# CPU.net
KiCad netlist of a schematic drawn in Altium Designer
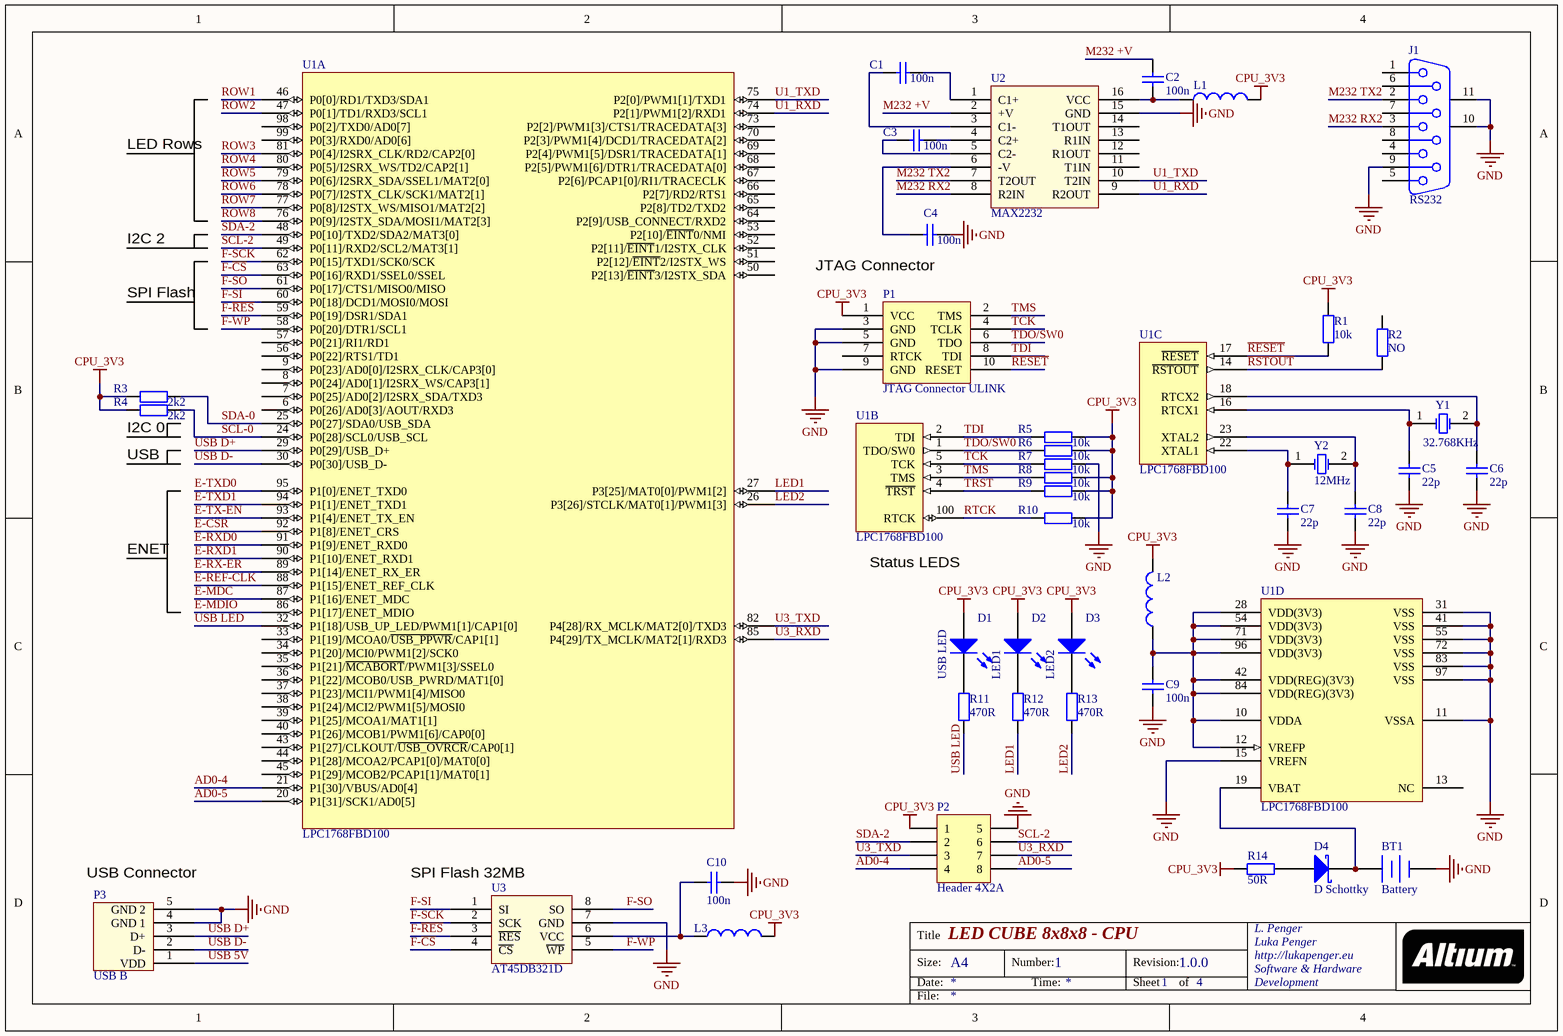
[diagram p0: CPU.SchDoc]

(export (version "E")
  (design (tool "Eeschema 10.0.6"))
  (components
    (comp (ref "BT1")
      (value "Battery")
      (footprint "Battery CAP")
      (description "Multicell Battery")
      (fields (field (name "PUBLISHER") "Altium Limited"))
      (libsource (lib "Miscellaneous Devices") (part "Battery"))
    )
    (comp (ref "C1")
      (value "100n")
      (footprint "1608[0603]")
      (description "Capacitor")
      (fields (field (name "PUBLISHER") "Altium Limited"))
      (libsource (lib "Miscellaneous Devices") (part "Cap"))
    )
    (comp (ref "C2")
      (value "100n")
      (footprint "1608[0603]")
      (description "Capacitor")
      (fields (field (name "PUBLISHER") "Altium Limited"))
      (libsource (lib "Miscellaneous Devices") (part "Cap"))
    )
    (comp (ref "C3")
      (value "100n")
      (footprint "1608[0603]")
      (description "Capacitor")
      (fields (field (name "PUBLISHER") "Altium Limited"))
      (libsource (lib "Miscellaneous Devices") (part "Cap"))
    )
    (comp (ref "C4")
      (value "100n")
      (footprint "1608[0603]")
      (description "Capacitor")
      (fields (field (name "PUBLISHER") "Altium Limited"))
      (libsource (lib "Miscellaneous Devices") (part "Cap"))
    )
    (comp (ref "C5")
      (value "22p")
      (footprint "1608[0603]")
      (description "Capacitor")
      (fields (field (name "PUBLISHER") "Altium Limited"))
      (libsource (lib "Miscellaneous Devices") (part "Cap"))
    )
    (comp (ref "C6")
      (value "22p")
      (footprint "1608[0603]")
      (description "Capacitor")
      (fields (field (name "PUBLISHER") "Altium Limited"))
      (libsource (lib "Miscellaneous Devices") (part "Cap"))
    )
    (comp (ref "C7")
      (value "22p")
      (footprint "1608[0603]")
      (description "Capacitor")
      (fields (field (name "PUBLISHER") "Altium Limited"))
      (libsource (lib "Miscellaneous Devices") (part "Cap"))
    )
    (comp (ref "C8")
      (value "22p")
      (footprint "1608[0603]")
      (description "Capacitor")
      (fields (field (name "PUBLISHER") "Altium Limited"))
      (libsource (lib "Miscellaneous Devices") (part "Cap"))
    )
    (comp (ref "C9")
      (value "100n")
      (footprint "1608[0603]")
      (description "Capacitor")
      (fields (field (name "PUBLISHER") "Altium Limited"))
      (libsource (lib "Miscellaneous Devices") (part "Cap"))
    )
    (comp (ref "C10")
      (value "100n")
      (footprint "1608[0603]")
      (description "Capacitor")
      (fields (field (name "PUBLISHER") "Altium Limited"))
      (libsource (lib "Miscellaneous Devices") (part "Cap"))
    )
    (comp (ref "D1")
      (value "USB LED")
      (footprint "LED-1")
      (description "Typical INFRARED GaAs LED")
      (fields (field (name "PUBLISHER") "Altium Limited"))
      (libsource (lib "Miscellaneous Devices") (part "LED0"))
    )
    (comp (ref "D2")
      (value "LED1")
      (footprint "LED-1")
      (description "Typical INFRARED GaAs LED")
      (fields (field (name "PUBLISHER") "Altium Limited"))
      (libsource (lib "Miscellaneous Devices") (part "LED0"))
    )
    (comp (ref "D3")
      (value "LED2")
      (footprint "LED-1")
      (description "Typical INFRARED GaAs LED")
      (fields (field (name "PUBLISHER") "Altium Limited"))
      (libsource (lib "Miscellaneous Devices") (part "LED0"))
    )
    (comp (ref "D4")
      (value "D Schottky")
      (footprint "SMB")
      (description "Schottky Diode")
      (fields (field (name "PUBLISHER") "Altium Limited"))
      (libsource (lib "Miscellaneous Devices") (part "D Schottky"))
    )
    (comp (ref "J1")
      (value "RS232")
      (footprint "DSUB1.385-2H9")
      (description "Receptacle Assembly, 9 Position, Right Angle")
      (fields (field (name "PUBLISHER") "Altium Limited"))
      (libsource (lib "Miscellaneous Connectors") (part "D Connector 9"))
    )
    (comp (ref "L1")
      (value "Inductor")
      (footprint "1608[0603]")
      (fields (field (name "PUBLISHER") "Altium Limited"))
      (libsource (lib "Miscellaneous Devices") (part "Inductor"))
    )
    (comp (ref "L2")
      (value "Inductor")
      (footprint "1608[0603]")
      (fields (field (name "PUBLISHER") "Altium Limited"))
      (libsource (lib "Miscellaneous Devices") (part "Inductor"))
    )
    (comp (ref "L3")
      (value "Inductor")
      (footprint "1608[0603]")
      (fields (field (name "PUBLISHER") "Altium Limited"))
      (libsource (lib "Miscellaneous Devices") (part "Inductor"))
    )
    (comp (ref "P1")
      (value "JTAG Connector ULINK")
      (footprint "JTAG Connector ULINK")
      (description "JTAG Connector")
      (libsource (lib "LP_Lib") (part "JTAG Connector ULINK"))
    )
    (comp (ref "P2")
      (value "Header 4X2A")
      (footprint "HDR2X4_CEN")
      (description "Header, 4-Pin, Dual row")
      (fields (field (name "PUBLISHER") "Altium Limited"))
      (libsource (lib "Miscellaneous Connectors") (part "Header 4X2A"))
    )
    (comp (ref "P3")
      (value "USB B")
      (footprint "USB B")
      (description "USB Connector")
      (libsource (lib "LP_Lib") (part "USB B"))
    )
    (comp (ref "R1")
      (value "10k")
      (footprint "1608[0603]")
      (description "Resistor")
      (fields (field (name "PUBLISHER") "Altium Limited"))
      (libsource (lib "") (part "Res2_1"))
    )
    (comp (ref "R2")
      (value "NO")
      (footprint "1608[0603]")
      (description "Resistor")
      (fields (field (name "PUBLISHER") "Altium Limited"))
      (libsource (lib "") (part "Res2_1"))
    )
    (comp (ref "R3")
      (value "2k2")
      (footprint "1608[0603]")
      (description "Resistor")
      (fields (field (name "PUBLISHER") "Altium Limited"))
      (libsource (lib "Miscellaneous Devices") (part "Res2"))
    )
    (comp (ref "R4")
      (value "2k2")
      (footprint "1608[0603]")
      (description "Resistor")
      (fields (field (name "PUBLISHER") "Altium Limited"))
      (libsource (lib "Miscellaneous Devices") (part "Res2"))
    )
    (comp (ref "R5")
      (value "10k")
      (footprint "1608[0603]")
      (description "Resistor")
      (fields (field (name "PUBLISHER") "Altium Limited"))
      (libsource (lib "Miscellaneous Devices") (part "Res2"))
    )
    (comp (ref "R6")
      (value "10k")
      (footprint "1608[0603]")
      (description "Resistor")
      (fields (field (name "PUBLISHER") "Altium Limited"))
      (libsource (lib "Miscellaneous Devices") (part "Res2"))
    )
    (comp (ref "R7")
      (value "10k")
      (footprint "1608[0603]")
      (description "Resistor")
      (fields (field (name "PUBLISHER") "Altium Limited"))
      (libsource (lib "Miscellaneous Devices") (part "Res2"))
    )
    (comp (ref "R8")
      (value "10k")
      (footprint "1608[0603]")
      (description "Resistor")
      (fields (field (name "PUBLISHER") "Altium Limited"))
      (libsource (lib "Miscellaneous Devices") (part "Res2"))
    )
    (comp (ref "R9")
      (value "10k")
      (footprint "1608[0603]")
      (description "Resistor")
      (fields (field (name "PUBLISHER") "Altium Limited"))
      (libsource (lib "Miscellaneous Devices") (part "Res2"))
    )
    (comp (ref "R10")
      (value "10k")
      (footprint "1608[0603]")
      (description "Resistor")
      (fields (field (name "PUBLISHER") "Altium Limited"))
      (libsource (lib "Miscellaneous Devices") (part "Res2"))
    )
    (comp (ref "R11")
      (value "470R")
      (footprint "1608[0603]")
      (description "Resistor")
      (fields (field (name "PUBLISHER") "Altium Limited"))
      (libsource (lib "") (part "Res2_1"))
    )
    (comp (ref "R12")
      (value "470R")
      (footprint "1608[0603]")
      (description "Resistor")
      (fields (field (name "PUBLISHER") "Altium Limited"))
      (libsource (lib "") (part "Res2_1"))
    )
    (comp (ref "R13")
      (value "470R")
      (footprint "1608[0603]")
      (description "Resistor")
      (fields (field (name "PUBLISHER") "Altium Limited"))
      (libsource (lib "") (part "Res2_1"))
    )
    (comp (ref "R14")
      (value "50R")
      (footprint "1608[0603]")
      (description "Resistor")
      (fields (field (name "PUBLISHER") "Altium Limited"))
      (libsource (lib "") (part "Res2_2"))
    )
    (comp (ref "U1")
      (value "LPC1768FBD100")
      (footprint "SOT407-1_N")
      (fields (field (name "PUBLISHER") "Altium Limited"))
      (libsource (lib "NXP LPC1768") (part "LPC1768FBD100"))
    )
    (comp (ref "U2")
      (value "MAX2232")
      (footprint "SOIC16_N")
      (description "Dual 232 +3V3")
      (libsource (lib "LP_Lib") (part "MAX2232"))
    )
    (comp (ref "U3")
      (value "AT45DB321D")
      (footprint "AT45DB321D")
      (description "SPI Flash 32MB")
      (libsource (lib "LP_Lib") (part "AT45DB321D"))
    )
    (comp (ref "Y1")
      (value "32.768KHz")
      (footprint "Crystal 4.1x1.5")
      (description "Crystal Oscillator")
      (fields (field (name "PUBLISHER") "Altium Limited"))
      (libsource (lib "Miscellaneous Devices") (part "XTAL"))
    )
    (comp (ref "Y2")
      (value "12MHz")
      (footprint "5x3.2 Crystal")
      (description "Crystal Oscillator")
      (fields (field (name "PUBLISHER") "Altium Limited"))
      (libsource (lib "Miscellaneous Devices") (part "XTAL"))
    )
  )
  (nets
    (net (code "1") (name "/AD0-4") (class "Default")
      (node (ref "P2") (pin "4") (pinfunction "4_4") (pintype "passive"))
      (node (ref "U1") (pin "21") (pinfunction "P1[30]/VBUS/AD0[4]_21") (pintype "bidirectional"))
    )
    (net (code "2") (name "/AD0-5") (class "Default")
      (node (ref "P2") (pin "8") (pinfunction "8_8") (pintype "passive"))
      (node (ref "U1") (pin "20") (pinfunction "P1[31]/SCK1/AD0[5]_20") (pintype "bidirectional"))
    )
    (net (code "3") (name "/E-CSR") (class "Default")
      (node (ref "U1") (pin "92") (pinfunction "P1[8]/ENET_CRS_92") (pintype "bidirectional"))
    )
    (net (code "4") (name "/E-MDC") (class "Default")
      (node (ref "U1") (pin "87") (pinfunction "P1[16]/ENET_MDC_87") (pintype "bidirectional"))
    )
    (net (code "5") (name "/E-MDIO") (class "Default")
      (node (ref "U1") (pin "86") (pinfunction "P1[17]/ENET_MDIO_86") (pintype "bidirectional"))
    )
    (net (code "6") (name "/E-REF-CLK") (class "Default")
      (node (ref "U1") (pin "88") (pinfunction "P1[15]/ENET_REF_CLK_88") (pintype "bidirectional"))
    )
    (net (code "7") (name "/E-RX-ER") (class "Default")
      (node (ref "U1") (pin "89") (pinfunction "P1[14]/ENET_RX_ER_89") (pintype "bidirectional"))
    )
    (net (code "8") (name "/E-RXD0") (class "Default")
      (node (ref "U1") (pin "91") (pinfunction "P1[9]/ENET_RXD0_91") (pintype "bidirectional"))
    )
    (net (code "9") (name "/E-RXD1") (class "Default")
      (node (ref "U1") (pin "90") (pinfunction "P1[10]/ENET_RXD1_90") (pintype "bidirectional"))
    )
    (net (code "10") (name "/E-TX-EN") (class "Default")
      (node (ref "U1") (pin "93") (pinfunction "P1[4]/ENET_TX_EN_93") (pintype "bidirectional"))
    )
    (net (code "11") (name "/E-TXD0") (class "Default")
      (node (ref "U1") (pin "95") (pinfunction "P1[0]/ENET_TXD0_95") (pintype "bidirectional"))
    )
    (net (code "12") (name "/E-TXD1") (class "Default")
      (node (ref "U1") (pin "94") (pinfunction "P1[1]/ENET_TXD1_94") (pintype "bidirectional"))
    )
    (net (code "13") (name "/F-SCK") (class "Default")
      (node (ref "U1") (pin "62") (pinfunction "P0[15]/TXD1/SCK0/SCK_62") (pintype "bidirectional"))
      (node (ref "U3") (pin "2") (pinfunction "SCK_2") (pintype "passive"))
    )
    (net (code "14") (name "/F-SI") (class "Default")
      (node (ref "U1") (pin "60") (pinfunction "P0[18]/DCD1/MOSI0/MOSI_60") (pintype "bidirectional"))
      (node (ref "U3") (pin "1") (pinfunction "SI_1") (pintype "passive"))
    )
    (net (code "15") (name "/F-SO") (class "Default")
      (node (ref "U1") (pin "61") (pinfunction "P0[17]/CTS1/MISO0/MISO_61") (pintype "bidirectional"))
      (node (ref "U3") (pin "8") (pinfunction "SO_8") (pintype "passive"))
    )
    (net (code "16") (name "/F-~{CS}") (class "Default")
      (node (ref "U1") (pin "63") (pinfunction "P0[16]/RXD1/SSEL0/SSEL_63") (pintype "bidirectional"))
      (node (ref "U3") (pin "4") (pinfunction "~{CS}_4") (pintype "passive"))
    )
    (net (code "17") (name "/F-~{RES}") (class "Default")
      (node (ref "U1") (pin "59") (pinfunction "P0[19]/DSR1/SDA1_59") (pintype "bidirectional"))
      (node (ref "U3") (pin "3") (pinfunction "~{RES}_3") (pintype "passive"))
    )
    (net (code "18") (name "/F-~{WP}") (class "Default")
      (node (ref "U1") (pin "58") (pinfunction "P0[20]/DTR1/SCL1_58") (pintype "bidirectional"))
      (node (ref "U3") (pin "5") (pinfunction "~{WP}_5") (pintype "passive"))
    )
    (net (code "19") (name "/LED1") (class "Default")
      (node (ref "R12") (pin "1") (pinfunction "1_1") (pintype "passive"))
      (node (ref "U1") (pin "27") (pinfunction "P3[25]/MAT0[0]/PWM1[2]_27") (pintype "bidirectional"))
    )
    (net (code "20") (name "/LED2") (class "Default")
      (node (ref "R13") (pin "1") (pinfunction "1_1") (pintype "passive"))
      (node (ref "U1") (pin "26") (pinfunction "P3[26]/STCLK/MAT0[1]/PWM1[3]_26") (pintype "bidirectional"))
    )
    (net (code "21") (name "/M232 +V") (class "Default")
      (node (ref "C2") (pin "1") (pinfunction "1_1") (pintype "passive"))
      (node (ref "U2") (pin "2") (pinfunction "+V_2") (pintype "passive"))
    )
    (net (code "22") (name "/M232 RX2") (class "Default")
      (node (ref "J1") (pin "3") (pinfunction "3_3") (pintype "passive"))
      (node (ref "U2") (pin "8") (pinfunction "R2IN_8") (pintype "passive"))
    )
    (net (code "23") (name "/M232 TX2") (class "Default")
      (node (ref "J1") (pin "2") (pinfunction "2_2") (pintype "passive"))
      (node (ref "U2") (pin "7") (pinfunction "T2OUT_7") (pintype "passive"))
    )
    (net (code "24") (name "/ROW1") (class "Default")
      (node (ref "U1") (pin "46") (pinfunction "P0[0]/RD1/TXD3/SDA1_46") (pintype "bidirectional"))
    )
    (net (code "25") (name "/ROW2") (class "Default")
      (node (ref "U1") (pin "47") (pinfunction "P0[1]/TD1/RXD3/SCL1_47") (pintype "bidirectional"))
    )
    (net (code "26") (name "/ROW3") (class "Default")
      (node (ref "U1") (pin "81") (pinfunction "P0[4]/I2SRX_CLK/RD2/CAP2[0]_81") (pintype "bidirectional"))
    )
    (net (code "27") (name "/ROW4") (class "Default")
      (node (ref "U1") (pin "80") (pinfunction "P0[5]/I2SRX_WS/TD2/CAP2[1]_80") (pintype "bidirectional"))
    )
    (net (code "28") (name "/ROW5") (class "Default")
      (node (ref "U1") (pin "79") (pinfunction "P0[6]/I2SRX_SDA/SSEL1/MAT2[0]_79") (pintype "bidirectional"))
    )
    (net (code "29") (name "/ROW6") (class "Default")
      (node (ref "U1") (pin "78") (pinfunction "P0[7]/I2STX_CLK/SCK1/MAT2[1]_78") (pintype "bidirectional"))
    )
    (net (code "30") (name "/ROW7") (class "Default")
      (node (ref "U1") (pin "77") (pinfunction "P0[8]/I2STX_WS/MISO1/MAT2[2]_77") (pintype "bidirectional"))
    )
    (net (code "31") (name "/ROW8") (class "Default")
      (node (ref "U1") (pin "76") (pinfunction "P0[9]/I2STX_SDA/MOSI1/MAT2[3]_76") (pintype "bidirectional"))
    )
    (net (code "32") (name "/RTCK") (class "Default")
      (node (ref "R10") (pin "1") (pinfunction "1_1") (pintype "passive"))
      (node (ref "U1") (pin "100") (pinfunction "RTCK_100") (pintype "bidirectional"))
    )
    (net (code "33") (name "/SCL-0") (class "Default")
      (node (ref "R4") (pin "2") (pinfunction "2_2") (pintype "passive"))
      (node (ref "U1") (pin "24") (pinfunction "P0[28]/SCL0/USB_SCL_24") (pintype "bidirectional"))
    )
    (net (code "34") (name "/SCL-2") (class "Default")
      (node (ref "P2") (pin "6") (pinfunction "6_6") (pintype "passive"))
      (node (ref "U1") (pin "49") (pinfunction "P0[11]/RXD2/SCL2/MAT3[1]_49") (pintype "bidirectional"))
    )
    (net (code "35") (name "/SDA-0") (class "Default")
      (node (ref "R3") (pin "2") (pinfunction "2_2") (pintype "passive"))
      (node (ref "U1") (pin "25") (pinfunction "P0[27]/SDA0/USB_SDA_25") (pintype "bidirectional"))
    )
    (net (code "36") (name "/SDA-2") (class "Default")
      (node (ref "P2") (pin "2") (pinfunction "2_2") (pintype "passive"))
      (node (ref "U1") (pin "48") (pinfunction "P0[10]/TXD2/SDA2/MAT3[0]_48") (pintype "bidirectional"))
    )
    (net (code "37") (name "/TCK") (class "Default")
      (node (ref "P1") (pin "4") (pinfunction "TCLK_4") (pintype "passive"))
      (node (ref "R7") (pin "1") (pinfunction "1_1") (pintype "passive"))
      (node (ref "U1") (pin "5") (pinfunction "TCK_5") (pintype "input"))
    )
    (net (code "38") (name "/TDI") (class "Default")
      (node (ref "P1") (pin "8") (pinfunction "TDI_8") (pintype "passive"))
      (node (ref "R5") (pin "1") (pinfunction "1_1") (pintype "passive"))
      (node (ref "U1") (pin "2") (pinfunction "TDI_2") (pintype "input"))
    )
    (net (code "39") (name "/TDO{slash}SW0") (class "Default")
      (node (ref "P1") (pin "6") (pinfunction "TDO_6") (pintype "passive"))
      (node (ref "R6") (pin "1") (pinfunction "1_1") (pintype "passive"))
      (node (ref "U1") (pin "1") (pinfunction "TDO/SW0_1") (pintype "output"))
    )
    (net (code "40") (name "/TMS") (class "Default")
      (node (ref "P1") (pin "2") (pinfunction "TMS_2") (pintype "passive"))
      (node (ref "R8") (pin "1") (pinfunction "1_1") (pintype "passive"))
      (node (ref "U1") (pin "3") (pinfunction "TMS_3") (pintype "input"))
    )
    (net (code "41") (name "/TRST") (class "Default")
      (node (ref "R9") (pin "1") (pinfunction "1_1") (pintype "passive"))
      (node (ref "U1") (pin "4") (pinfunction "~{TRST}_4") (pintype "input"))
    )
    (net (code "42") (name "/U1_RXD") (class "Default")
      (node (ref "U1") (pin "74") (pinfunction "P2[1]/PWM1[2]/RXD1_74") (pintype "bidirectional"))
      (node (ref "U2") (pin "9") (pinfunction "R2OUT_9") (pintype "passive"))
    )
    (net (code "43") (name "/U1_TXD") (class "Default")
      (node (ref "U1") (pin "75") (pinfunction "P2[0]/PWM1[1]/TXD1_75") (pintype "bidirectional"))
      (node (ref "U2") (pin "10") (pinfunction "T2IN_10") (pintype "passive"))
    )
    (net (code "44") (name "/U3_RXD") (class "Default")
      (node (ref "P2") (pin "7") (pinfunction "7_7") (pintype "passive"))
      (node (ref "U1") (pin "85") (pinfunction "P4[29]/TX_MCLK/MAT2[1]/RXD3_85") (pintype "bidirectional"))
    )
    (net (code "45") (name "/U3_TXD") (class "Default")
      (node (ref "P2") (pin "3") (pinfunction "3_3") (pintype "passive"))
      (node (ref "U1") (pin "82") (pinfunction "P4[28]/RX_MCLK/MAT2[0]/TXD3_82") (pintype "bidirectional"))
    )
    (net (code "46") (name "/USB 5V") (class "Default")
      (node (ref "P3") (pin "1") (pinfunction "VDD_1") (pintype "passive"))
    )
    (net (code "47") (name "/USB D+") (class "Default")
      (node (ref "P3") (pin "3") (pinfunction "D+_3") (pintype "passive"))
      (node (ref "U1") (pin "29") (pinfunction "P0[29]/USB_D+_29") (pintype "bidirectional"))
    )
    (net (code "48") (name "/USB D-") (class "Default")
      (node (ref "P3") (pin "2") (pinfunction "D-_2") (pintype "passive"))
      (node (ref "U1") (pin "30") (pinfunction "P0[30]/USB_D-_30") (pintype "bidirectional"))
    )
    (net (code "49") (name "/USB LED") (class "Default")
      (node (ref "R11") (pin "1") (pinfunction "1_1") (pintype "passive"))
      (node (ref "U1") (pin "32") (pinfunction "P1[18]/USB_UP_LED/PWM1[1]/CAP1[0]_32") (pintype "bidirectional"))
    )
    (net (code "50") (name "/~{RESET}") (class "Default")
      (node (ref "P1") (pin "10") (pinfunction "RESET_10") (pintype "passive"))
      (node (ref "R1") (pin "1") (pinfunction "1_1") (pintype "passive"))
      (node (ref "U1") (pin "17") (pinfunction "~{RESET}_17") (pintype "input"))
    )
    (net (code "51") (name "/~{RSTOUT}") (class "Default")
      (node (ref "R2") (pin "1") (pinfunction "1_1") (pintype "passive"))
      (node (ref "U1") (pin "14") (pinfunction "~{RSTOUT}_14") (pintype "output"))
    )
    (net (code "52") (name "CPU_3V3") (class "Default")
      (node (ref "D1") (pin "1") (pinfunction "A_1") (pintype "passive"))
      (node (ref "D2") (pin "1") (pinfunction "A_1") (pintype "passive"))
      (node (ref "D3") (pin "1") (pinfunction "A_1") (pintype "passive"))
      (node (ref "L1") (pin "2") (pinfunction "2_2") (pintype "passive"))
      (node (ref "L2") (pin "2") (pinfunction "2_2") (pintype "passive"))
      (node (ref "L3") (pin "2") (pinfunction "2_2") (pintype "passive"))
      (node (ref "P1") (pin "1") (pinfunction "VCC_1") (pintype "passive"))
      (node (ref "P2") (pin "1") (pinfunction "1_1") (pintype "passive"))
      (node (ref "R1") (pin "2") (pinfunction "2_2") (pintype "passive"))
      (node (ref "R10") (pin "2") (pinfunction "2_2") (pintype "passive"))
      (node (ref "R14") (pin "2") (pinfunction "2_2") (pintype "passive"))
      (node (ref "R3") (pin "1") (pinfunction "1_1") (pintype "passive"))
      (node (ref "R4") (pin "1") (pinfunction "1_1") (pintype "passive"))
      (node (ref "R5") (pin "2") (pinfunction "2_2") (pintype "passive"))
      (node (ref "R6") (pin "2") (pinfunction "2_2") (pintype "passive"))
      (node (ref "R8") (pin "2") (pinfunction "2_2") (pintype "passive"))
      (node (ref "R9") (pin "2") (pinfunction "2_2") (pintype "passive"))
    )
    (net (code "53") (name "GND") (class "Default")
      (node (ref "BT1") (pin "2") (pinfunction "-_2") (pintype "passive"))
      (node (ref "C10") (pin "1") (pinfunction "1_1") (pintype "passive"))
      (node (ref "C4") (pin "1") (pinfunction "1_1") (pintype "passive"))
      (node (ref "C5") (pin "1") (pinfunction "1_1") (pintype "passive"))
      (node (ref "C6") (pin "1") (pinfunction "1_1") (pintype "passive"))
      (node (ref "C7") (pin "1") (pinfunction "1_1") (pintype "passive"))
      (node (ref "C8") (pin "1") (pinfunction "1_1") (pintype "passive"))
      (node (ref "C9") (pin "1") (pinfunction "1_1") (pintype "passive"))
      (node (ref "J1") (pin "10") (pinfunction "MH1_10") (pintype "passive"))
      (node (ref "J1") (pin "11") (pinfunction "MH2_11") (pintype "passive"))
      (node (ref "J1") (pin "9") (pinfunction "9_9") (pintype "passive"))
      (node (ref "P1") (pin "3") (pinfunction "GND_3") (pintype "passive"))
      (node (ref "P1") (pin "5") (pinfunction "GND_5") (pintype "passive"))
      (node (ref "P1") (pin "9") (pinfunction "GND_9") (pintype "passive"))
      (node (ref "P2") (pin "5") (pinfunction "5_5") (pintype "passive"))
      (node (ref "P3") (pin "4") (pinfunction "GND_1_4") (pintype "passive"))
      (node (ref "P3") (pin "5") (pinfunction "GND_2_5") (pintype "passive"))
      (node (ref "R7") (pin "2") (pinfunction "2_2") (pintype "passive"))
      (node (ref "U1") (pin "11") (pinfunction "VSSA_11") (pintype "power_in"))
      (node (ref "U1") (pin "15") (pinfunction "VREFN_15") (pintype "power_in"))
      (node (ref "U1") (pin "31") (pinfunction "VSS_31") (pintype "power_in"))
      (node (ref "U1") (pin "41") (pinfunction "VSS_41") (pintype "power_in"))
      (node (ref "U1") (pin "55") (pinfunction "VSS_55") (pintype "power_in"))
      (node (ref "U1") (pin "72") (pinfunction "VSS_72") (pintype "power_in"))
      (node (ref "U1") (pin "83") (pinfunction "VSS_83") (pintype "power_in"))
      (node (ref "U1") (pin "97") (pinfunction "VSS_97") (pintype "power_in"))
      (node (ref "U2") (pin "15") (pinfunction "GND_15") (pintype "passive"))
      (node (ref "U3") (pin "7") (pinfunction "GND_7") (pintype "passive"))
    )
    (net (code "54") (name "Net-(BT1-+)") (class "Default")
      (node (ref "BT1") (pin "1") (pinfunction "+_1") (pintype "passive"))
      (node (ref "D4") (pin "2") (pinfunction "K_2") (pintype "passive"))
      (node (ref "U1") (pin "19") (pinfunction "VBAT_19") (pintype "power_in"))
    )
    (net (code "55") (name "Net-(D1-K)") (class "Default")
      (node (ref "D1") (pin "2") (pinfunction "K_2") (pintype "passive"))
      (node (ref "R11") (pin "2") (pinfunction "2_2") (pintype "passive"))
    )
    (net (code "56") (name "Net-(D2-K)") (class "Default")
      (node (ref "D2") (pin "2") (pinfunction "K_2") (pintype "passive"))
      (node (ref "R12") (pin "2") (pinfunction "2_2") (pintype "passive"))
    )
    (net (code "57") (name "Net-(D3-K)") (class "Default")
      (node (ref "D3") (pin "2") (pinfunction "K_2") (pintype "passive"))
      (node (ref "R13") (pin "2") (pinfunction "2_2") (pintype "passive"))
    )
    (net (code "58") (name "Net-(D4-A)") (class "Default")
      (node (ref "D4") (pin "1") (pinfunction "A_1") (pintype "passive"))
      (node (ref "R14") (pin "1") (pinfunction "1_1") (pintype "passive"))
    )
    (net (code "59") (name "Net-(U1C-RTCX1)") (class "Default")
      (node (ref "C5") (pin "2") (pinfunction "2_2") (pintype "passive"))
      (node (ref "U1") (pin "16") (pinfunction "RTCX1_16") (pintype "input"))
      (node (ref "Y1") (pin "1") (pinfunction "OSC1_1") (pintype "passive"))
    )
    (net (code "60") (name "Net-(U1C-RTCX2)") (class "Default")
      (node (ref "C6") (pin "2") (pinfunction "2_2") (pintype "passive"))
      (node (ref "U1") (pin "18") (pinfunction "RTCX2_18") (pintype "output"))
      (node (ref "Y1") (pin "2") (pinfunction "OSC2_2") (pintype "passive"))
    )
    (net (code "61") (name "Net-(U1C-XTAL1)") (class "Default")
      (node (ref "C7") (pin "2") (pinfunction "2_2") (pintype "passive"))
      (node (ref "U1") (pin "22") (pinfunction "XTAL1_22") (pintype "input"))
      (node (ref "Y2") (pin "1") (pinfunction "OSC1_1") (pintype "passive"))
    )
    (net (code "62") (name "Net-(U1C-XTAL2)") (class "Default")
      (node (ref "C8") (pin "2") (pinfunction "2_2") (pintype "passive"))
      (node (ref "U1") (pin "23") (pinfunction "XTAL2_23") (pintype "output"))
      (node (ref "Y2") (pin "2") (pinfunction "OSC2_2") (pintype "passive"))
    )
    (net (code "63") (name "Net-(U1D-VDDA)") (class "Default")
      (node (ref "C9") (pin "2") (pinfunction "2_2") (pintype "passive"))
      (node (ref "L2") (pin "1") (pinfunction "1_1") (pintype "passive"))
      (node (ref "U1") (pin "10") (pinfunction "VDDA_10") (pintype "power_in"))
      (node (ref "U1") (pin "12") (pinfunction "VREFP_12") (pintype "input"))
      (node (ref "U1") (pin "28") (pinfunction "VDD(3V3)_28") (pintype "power_in"))
      (node (ref "U1") (pin "42") (pinfunction "VDD(REG)(3V3)_42") (pintype "power_in"))
      (node (ref "U1") (pin "54") (pinfunction "VDD(3V3)_54") (pintype "power_in"))
      (node (ref "U1") (pin "71") (pinfunction "VDD(3V3)_71") (pintype "power_in"))
      (node (ref "U1") (pin "84") (pinfunction "VDD(REG)(3V3)_84") (pintype "power_in"))
      (node (ref "U1") (pin "96") (pinfunction "VDD(3V3)_96") (pintype "power_in"))
    )
    (net (code "64") (name "Net-(U2--V)") (class "Default")
      (node (ref "C4") (pin "2") (pinfunction "2_2") (pintype "passive"))
      (node (ref "U2") (pin "6") (pinfunction "-V_6") (pintype "passive"))
    )
    (net (code "65") (name "Net-(U2-C1+)") (class "Default")
      (node (ref "C1") (pin "2") (pinfunction "2_2") (pintype "passive"))
      (node (ref "U2") (pin "1") (pinfunction "C1+_1") (pintype "passive"))
    )
    (net (code "66") (name "Net-(U2-C1-)") (class "Default")
      (node (ref "C1") (pin "1") (pinfunction "1_1") (pintype "passive"))
      (node (ref "U2") (pin "3") (pinfunction "C1-_3") (pintype "passive"))
    )
    (net (code "67") (name "Net-(U2-C2+)") (class "Default")
      (node (ref "C3") (pin "2") (pinfunction "2_2") (pintype "passive"))
      (node (ref "U2") (pin "4") (pinfunction "C2+_4") (pintype "passive"))
    )
    (net (code "68") (name "Net-(U2-C2-)") (class "Default")
      (node (ref "C3") (pin "1") (pinfunction "1_1") (pintype "passive"))
      (node (ref "U2") (pin "5") (pinfunction "C2-_5") (pintype "passive"))
    )
    (net (code "69") (name "Net-(U2-VCC)") (class "Default")
      (node (ref "C2") (pin "2") (pinfunction "2_2") (pintype "passive"))
      (node (ref "L1") (pin "1") (pinfunction "1_1") (pintype "passive"))
      (node (ref "U2") (pin "16") (pinfunction "VCC_16") (pintype "passive"))
    )
    (net (code "70") (name "Net-(U3-VCC)") (class "Default")
      (node (ref "C10") (pin "2") (pinfunction "2_2") (pintype "passive"))
      (node (ref "L3") (pin "1") (pinfunction "1_1") (pintype "passive"))
      (node (ref "U3") (pin "6") (pinfunction "VCC_6") (pintype "passive"))
    )
    (net (code "71") (name "unconnected-(J1-Pad1)") (class "Default")
      (node (ref "J1") (pin "1") (pinfunction "1_1") (pintype "passive"))
    )
    (net (code "72") (name "unconnected-(J1-Pad4)") (class "Default")
      (node (ref "J1") (pin "4") (pinfunction "4_4") (pintype "passive"))
    )
    (net (code "73") (name "unconnected-(J1-Pad5)") (class "Default")
      (node (ref "J1") (pin "5") (pinfunction "5_5") (pintype "passive"))
    )
    (net (code "74") (name "unconnected-(J1-Pad6)") (class "Default")
      (node (ref "J1") (pin "6") (pinfunction "6_6") (pintype "passive"))
    )
    (net (code "75") (name "unconnected-(J1-Pad7)") (class "Default")
      (node (ref "J1") (pin "7") (pinfunction "7_7") (pintype "passive"))
    )
    (net (code "76") (name "unconnected-(J1-Pad8)") (class "Default")
      (node (ref "J1") (pin "8") (pinfunction "8_8") (pintype "passive"))
    )
    (net (code "77") (name "unconnected-(P1-RTCK-Pad7)") (class "Default")
      (node (ref "P1") (pin "7") (pinfunction "RTCK_7") (pintype "passive"))
    )
    (net (code "78") (name "unconnected-(R2-Pad2)") (class "Default")
      (node (ref "R2") (pin "2") (pinfunction "2_2") (pintype "passive"))
    )
    (net (code "79") (name "unconnected-(U1A-P0[2]{slash}TXD0{slash}AD0[7]-Pad98)") (class "Default")
      (node (ref "U1") (pin "98") (pinfunction "P0[2]/TXD0/AD0[7]_98") (pintype "bidirectional"))
    )
    (net (code "80") (name "unconnected-(U1A-P0[3]{slash}RXD0{slash}AD0[6]-Pad99)") (class "Default")
      (node (ref "U1") (pin "99") (pinfunction "P0[3]/RXD0/AD0[6]_99") (pintype "bidirectional"))
    )
    (net (code "81") (name "unconnected-(U1A-P0[21]{slash}RI1{slash}RD1-Pad57)") (class "Default")
      (node (ref "U1") (pin "57") (pinfunction "P0[21]/RI1/RD1_57") (pintype "bidirectional"))
    )
    (net (code "82") (name "unconnected-(U1A-P0[22]{slash}RTS1{slash}TD1-Pad56)") (class "Default")
      (node (ref "U1") (pin "56") (pinfunction "P0[22]/RTS1/TD1_56") (pintype "bidirectional"))
    )
    (net (code "83") (name "unconnected-(U1A-P0[23]{slash}AD0[0]{slash}I2SRX_CLK{slash}CAP3[0]-Pad9)") (class "Default")
      (node (ref "U1") (pin "9") (pinfunction "P0[23]/AD0[0]/I2SRX_CLK/CAP3[0]_9") (pintype "bidirectional"))
    )
    (net (code "84") (name "unconnected-(U1A-P0[24]{slash}AD0[1]{slash}I2SRX_WS{slash}CAP3[1]-Pad8)") (class "Default")
      (node (ref "U1") (pin "8") (pinfunction "P0[24]/AD0[1]/I2SRX_WS/CAP3[1]_8") (pintype "bidirectional"))
    )
    (net (code "85") (name "unconnected-(U1A-P0[25]{slash}AD0[2]{slash}I2SRX_SDA{slash}TXD3-Pad7)") (class "Default")
      (node (ref "U1") (pin "7") (pinfunction "P0[25]/AD0[2]/I2SRX_SDA/TXD3_7") (pintype "bidirectional"))
    )
    (net (code "86") (name "unconnected-(U1A-P0[26]{slash}AD0[3]{slash}AOUT{slash}RXD3-Pad6)") (class "Default")
      (node (ref "U1") (pin "6") (pinfunction "P0[26]/AD0[3]/AOUT/RXD3_6") (pintype "bidirectional"))
    )
    (net (code "87") (name "unconnected-(U1A-P1[19]{slash}MCOA0{slash}~{USB_PPWR}{slash}CAP1[1]-Pad33)") (class "Default")
      (node (ref "U1") (pin "33") (pinfunction "P1[19]/MCOA0/~{USB_PPWR}/CAP1[1]_33") (pintype "bidirectional"))
    )
    (net (code "88") (name "unconnected-(U1A-P1[20]{slash}MCI0{slash}PWM1[2]{slash}SCK0-Pad34)") (class "Default")
      (node (ref "U1") (pin "34") (pinfunction "P1[20]/MCI0/PWM1[2]/SCK0_34") (pintype "bidirectional"))
    )
    (net (code "89") (name "unconnected-(U1A-P1[21]{slash}~{MCABORT}{slash}PWM1[3]{slash}SSEL0-Pad35)") (class "Default")
      (node (ref "U1") (pin "35") (pinfunction "P1[21]/~{MCABORT}/PWM1[3]/SSEL0_35") (pintype "bidirectional"))
    )
    (net (code "90") (name "unconnected-(U1A-P1[22]{slash}MCOB0{slash}USB_PWRD{slash}MAT1[0]-Pad36)") (class "Default")
      (node (ref "U1") (pin "36") (pinfunction "P1[22]/MCOB0/USB_PWRD/MAT1[0]_36") (pintype "bidirectional"))
    )
    (net (code "91") (name "unconnected-(U1A-P1[23]{slash}MCI1{slash}PWM1[4]{slash}MISO0-Pad37)") (class "Default")
      (node (ref "U1") (pin "37") (pinfunction "P1[23]/MCI1/PWM1[4]/MISO0_37") (pintype "bidirectional"))
    )
    (net (code "92") (name "unconnected-(U1A-P1[24]{slash}MCI2{slash}PWM1[5]{slash}MOSI0-Pad38)") (class "Default")
      (node (ref "U1") (pin "38") (pinfunction "P1[24]/MCI2/PWM1[5]/MOSI0_38") (pintype "bidirectional"))
    )
    (net (code "93") (name "unconnected-(U1A-P1[25]{slash}MCOA1{slash}MAT1[1]-Pad39)") (class "Default")
      (node (ref "U1") (pin "39") (pinfunction "P1[25]/MCOA1/MAT1[1]_39") (pintype "bidirectional"))
    )
    (net (code "94") (name "unconnected-(U1A-P1[26]{slash}MCOB1{slash}PWM1[6]{slash}CAP0[0]-Pad40)") (class "Default")
      (node (ref "U1") (pin "40") (pinfunction "P1[26]/MCOB1/PWM1[6]/CAP0[0]_40") (pintype "bidirectional"))
    )
    (net (code "95") (name "unconnected-(U1A-P1[27]{slash}CLKOUT{slash}~{USB_OVRCR}{slash}CAP0[1]-Pad43)") (class "Default")
      (node (ref "U1") (pin "43") (pinfunction "P1[27]/CLKOUT/~{USB_OVRCR}/CAP0[1]_43") (pintype "bidirectional"))
    )
    (net (code "96") (name "unconnected-(U1A-P1[28]{slash}MCOA2{slash}PCAP1[0]{slash}MAT0[0]-Pad44)") (class "Default")
      (node (ref "U1") (pin "44") (pinfunction "P1[28]/MCOA2/PCAP1[0]/MAT0[0]_44") (pintype "bidirectional"))
    )
    (net (code "97") (name "unconnected-(U1A-P1[29]{slash}MCOB2{slash}PCAP1[1]{slash}MAT0[1]-Pad45)") (class "Default")
      (node (ref "U1") (pin "45") (pinfunction "P1[29]/MCOB2/PCAP1[1]/MAT0[1]_45") (pintype "bidirectional"))
    )
    (net (code "98") (name "unconnected-(U1A-P2[2]{slash}PWM1[3]{slash}CTS1{slash}TRACEDATA[3]-Pad73)") (class "Default")
      (node (ref "U1") (pin "73") (pinfunction "P2[2]/PWM1[3]/CTS1/TRACEDATA[3]_73") (pintype "bidirectional"))
    )
    (net (code "99") (name "unconnected-(U1A-P2[3]{slash}PWM1[4]{slash}DCD1{slash}TRACEDATA[2]-Pad70)") (class "Default")
      (node (ref "U1") (pin "70") (pinfunction "P2[3]/PWM1[4]/DCD1/TRACEDATA[2]_70") (pintype "bidirectional"))
    )
    (net (code "100") (name "unconnected-(U1A-P2[4]{slash}PWM1[5]{slash}DSR1{slash}TRACEDATA[1]-Pad69)") (class "Default")
      (node (ref "U1") (pin "69") (pinfunction "P2[4]/PWM1[5]/DSR1/TRACEDATA[1]_69") (pintype "bidirectional"))
    )
    (net (code "101") (name "unconnected-(U1A-P2[5]{slash}PWM1[6]{slash}DTR1{slash}TRACEDATA[0]-Pad68)") (class "Default")
      (node (ref "U1") (pin "68") (pinfunction "P2[5]/PWM1[6]/DTR1/TRACEDATA[0]_68") (pintype "bidirectional"))
    )
    (net (code "102") (name "unconnected-(U1A-P2[6]{slash}PCAP1[0]{slash}RI1{slash}TRACECLK-Pad67)") (class "Default")
      (node (ref "U1") (pin "67") (pinfunction "P2[6]/PCAP1[0]/RI1/TRACECLK_67") (pintype "bidirectional"))
    )
    (net (code "103") (name "unconnected-(U1A-P2[7]{slash}RD2{slash}RTS1-Pad66)") (class "Default")
      (node (ref "U1") (pin "66") (pinfunction "P2[7]/RD2/RTS1_66") (pintype "bidirectional"))
    )
    (net (code "104") (name "unconnected-(U1A-P2[8]{slash}TD2{slash}TXD2-Pad65)") (class "Default")
      (node (ref "U1") (pin "65") (pinfunction "P2[8]/TD2/TXD2_65") (pintype "bidirectional"))
    )
    (net (code "105") (name "unconnected-(U1A-P2[9]{slash}USB_CONNECT{slash}RXD2-Pad64)") (class "Default")
      (node (ref "U1") (pin "64") (pinfunction "P2[9]/USB_CONNECT/RXD2_64") (pintype "bidirectional"))
    )
    (net (code "106") (name "unconnected-(U1A-P2[10]{slash}~{EINT}0{slash}NMI-Pad53)") (class "Default")
      (node (ref "U1") (pin "53") (pinfunction "P2[10]/~{EINT}0/NMI_53") (pintype "bidirectional"))
    )
    (net (code "107") (name "unconnected-(U1A-P2[11]{slash}~{EINT}1{slash}I2STX_CLK-Pad52)") (class "Default")
      (node (ref "U1") (pin "52") (pinfunction "P2[11]/~{EINT}1/I2STX_CLK_52") (pintype "bidirectional"))
    )
    (net (code "108") (name "unconnected-(U1A-P2[12]{slash}~{EINT}2{slash}I2STX_WS-Pad51)") (class "Default")
      (node (ref "U1") (pin "51") (pinfunction "P2[12]/~{EINT}2/I2STX_WS_51") (pintype "bidirectional"))
    )
    (net (code "109") (name "unconnected-(U1A-P2[13]{slash}~{EINT}3{slash}I2STX_SDA-Pad50)") (class "Default")
      (node (ref "U1") (pin "50") (pinfunction "P2[13]/~{EINT}3/I2STX_SDA_50") (pintype "bidirectional"))
    )
    (net (code "110") (name "unconnected-(U1D-NC-Pad13)") (class "Default")
      (node (ref "U1") (pin "13") (pinfunction "NC_13") (pintype "power_in"))
    )
    (net (code "111") (name "unconnected-(U2-R1IN-Pad13)") (class "Default")
      (node (ref "U2") (pin "13") (pinfunction "R1IN_13") (pintype "passive"))
    )
    (net (code "112") (name "unconnected-(U2-R1OUT-Pad12)") (class "Default")
      (node (ref "U2") (pin "12") (pinfunction "R1OUT_12") (pintype "passive"))
    )
    (net (code "113") (name "unconnected-(U2-T1IN-Pad11)") (class "Default")
      (node (ref "U2") (pin "11") (pinfunction "T1IN_11") (pintype "passive"))
    )
    (net (code "114") (name "unconnected-(U2-T1OUT-Pad14)") (class "Default")
      (node (ref "U2") (pin "14") (pinfunction "T1OUT_14") (pintype "passive"))
    )
  )
)
